# LDO_3v3_LM2937.net
KiCad netlist of a schematic drawn in Altium Designer
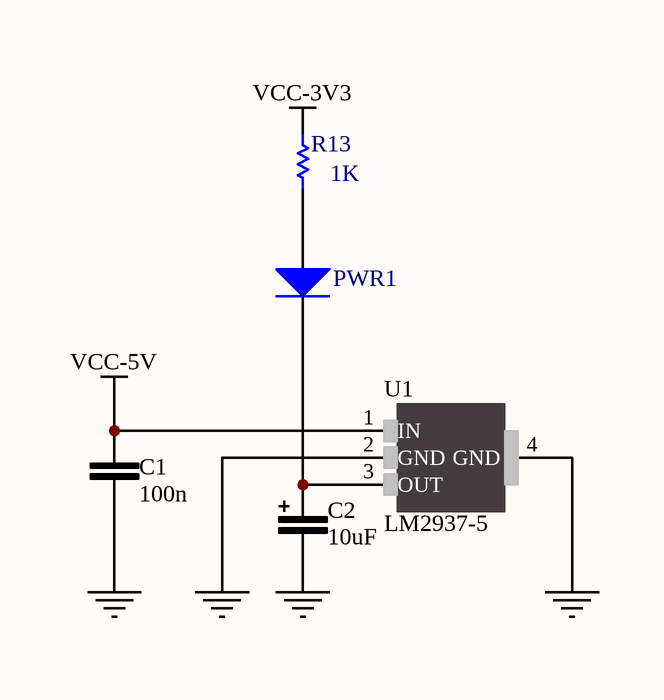
[diagram p0: LDO_3v3_LM2937.SchDoc]

(export (version "E")
  (design (tool "Eeschema 10.0.6"))
  (components
    (comp (ref "C1")
      (value "100n")
      (footprint "CER_0603")
      (description "CAP CER 100n 10V X5R 10% 0603")
      (libsource (lib "Capacitors") (part "06032105"))
    )
    (comp (ref "C2")
      (value "10uF")
      (footprint "TANT_1210")
      (description "CAP TANT 10u")
      (libsource (lib "Capacitors") (part "00001106"))
    )
    (comp (ref "PWR1")
      (value "~")
      (footprint "SMC")
      (description "Default Diode")
      (fields (field (name "PUBLISHER") "Altium Limited"))
      (libsource (lib "Miscellaneous Devices") (part "Diode"))
    )
    (comp (ref "R13")
      (value "1K")
      (footprint "AXIAL-0.3")
      (description "Resistor")
      (fields (field (name "PUBLISHER") "Altium Limited"))
      (libsource (lib "Miscellaneous Devices") (part "Res1"))
    )
    (comp (ref "U1")
      (value "LM2937-5")
      (footprint "SOT223")
      (description "IC REG LINEAR 5V 400MA SOT223-4")
      (libsource (lib "Integrated_circuits") (part "00000007"))
    )
  )
  (nets
    (net (code "1") (name "GND") (class "Default")
      (node (ref "C1") (pin "1") (pinfunction "1_1") (pintype "passive"))
      (node (ref "C2") (pin "2") (pinfunction "2_2") (pintype "passive"))
      (node (ref "U1") (pin "2") (pinfunction "GND_2") (pintype "passive"))
      (node (ref "U1") (pin "4") (pinfunction "GND_4") (pintype "passive"))
    )
    (net (code "2") (name "Net-(PWR1-A)") (class "Default")
      (node (ref "PWR1") (pin "1") (pinfunction "A_1") (pintype "passive"))
      (node (ref "R13") (pin "1") (pinfunction "1_1") (pintype "passive"))
    )
    (net (code "3") (name "Net-(PWR1-K)") (class "Default")
      (node (ref "C2") (pin "1") (pinfunction "1_1") (pintype "passive"))
      (node (ref "PWR1") (pin "2") (pinfunction "K_2") (pintype "passive"))
      (node (ref "U1") (pin "3") (pinfunction "OUT_3") (pintype "passive"))
    )
    (net (code "5") (name "VCC-5V") (class "Default")
      (node (ref "C1") (pin "2") (pinfunction "2_2") (pintype "passive"))
      (node (ref "U1") (pin "1") (pinfunction "IN_1") (pintype "passive"))
    )
    (net (code "6") (name "unconnected-(R13-Pad2)") (class "Default")
      (node (ref "R13") (pin "2") (pinfunction "2_2") (pintype "passive"))
    )
  )
)
